# IMU.net
KiCad netlist of a schematic drawn in Altium Designer
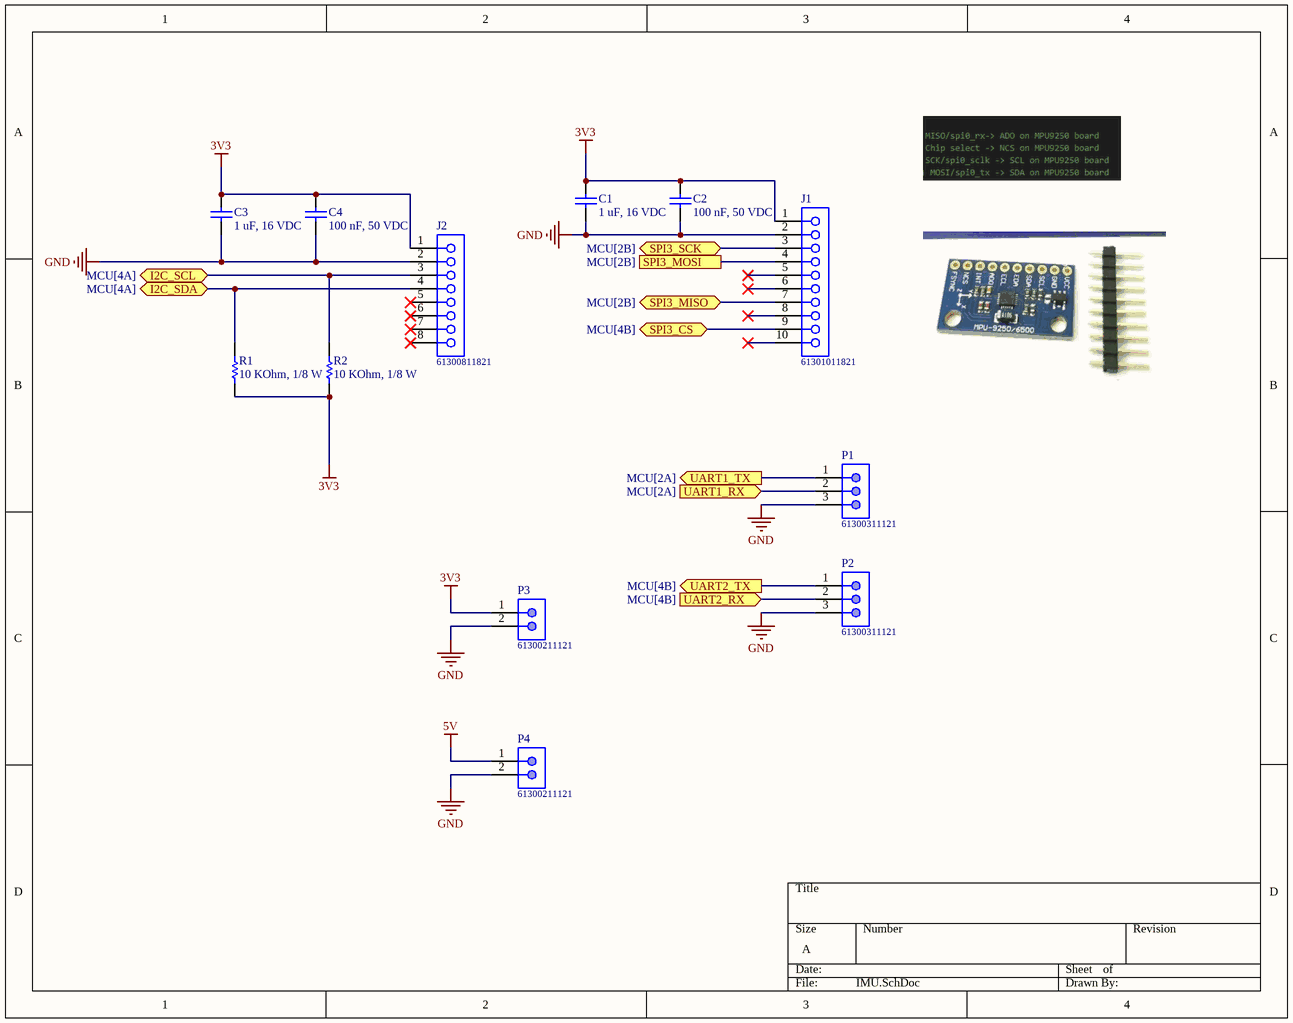
[diagram p0: IMU.SchDoc]

(export (version "E")
  (design (tool "Eeschema 10.0.6"))
  (components
    (comp (ref "C1")
      (value "1 uF, 16 VDC")
      (footprint "CAP_0805")
      (description "CAP, size 0805, 1 uF, 16 VDC")
      (fields (field (name "TOLERANCE") "+/-10%"))
      (libsource (lib "Altium_Ceramic_Cap") (part "0108051051016"))
    )
    (comp (ref "C2")
      (value "100 nF, 50 VDC")
      (footprint "CAP_0805")
      (description "CAP, size 0805, 100 nF, 50 VDC")
      (fields (field (name "TOLERANCE") "+/-5%"))
      (libsource (lib "Altium_Ceramic_Cap") (part "0108051031050"))
    )
    (comp (ref "C3")
      (value "1 uF, 16 VDC")
      (footprint "CAP_0805")
      (description "CAP, size 0805, 1 uF, 16 VDC")
      (fields (field (name "TOLERANCE") "+/-10%"))
      (libsource (lib "Altium_Ceramic_Cap") (part "0108051051016"))
    )
    (comp (ref "C4")
      (value "100 nF, 50 VDC")
      (footprint "CAP_0805")
      (description "CAP, size 0805, 100 nF, 50 VDC")
      (fields (field (name "TOLERANCE") "+/-5%"))
      (libsource (lib "Altium_Ceramic_Cap") (part "0108051031050"))
    )
    (comp (ref "J1")
      (value "61301011821")
      (footprint "61301011821")
      (description "WR-PHD Socket Header, THT, pitch 2.54mm, Single Row, Vertical, 10p")
      (fields (field (name "MANUFACTURER") "Wurth Elektronik"))
      (libsource (lib "Altium_Header") (part "61301011821"))
    )
    (comp (ref "J2")
      (value "61300811821")
      (footprint "61300811821")
      (description "WR-PHD Socket Header, THT, pitch 2.54mm, Single Row, Vertical, 8p")
      (fields (field (name "MANUFACTURER") "Wurth Elektronik"))
      (libsource (lib "Altium_Header") (part "61300811821"))
    )
    (comp (ref "P1")
      (value "61300311121")
      (footprint "61300311121")
      (description "WR-PHD Pin Header, THT, pitch 2.54mm, Single Row, Vertical, 3p")
      (fields (field (name "MANUFACTURER") "Wurth Elektronik"))
      (libsource (lib "Altium_Header") (part "61300311121"))
    )
    (comp (ref "P2")
      (value "61300311121")
      (footprint "61300311121")
      (description "WR-PHD Pin Header, THT, pitch 2.54mm, Single Row, Vertical, 3p")
      (fields (field (name "MANUFACTURER") "Wurth Elektronik"))
      (libsource (lib "Altium_Header") (part "61300311121"))
    )
    (comp (ref "P3")
      (value "61300211121")
      (footprint "61300211121")
      (description "WR-PHD Pin Header, THT, pitch 2.54mm, Single Row, Vertical, 2p")
      (fields (field (name "MANUFACTURER") "Wurth Elektronik"))
      (libsource (lib "Altium_Header") (part "61300211121"))
    )
    (comp (ref "P4")
      (value "61300211121")
      (footprint "61300211121")
      (description "WR-PHD Pin Header, THT, pitch 2.54mm, Single Row, Vertical, 2p")
      (fields (field (name "MANUFACTURER") "Wurth Elektronik"))
      (libsource (lib "Altium_Header") (part "61300211121"))
    )
    (comp (ref "R1")
      (value "10 KOhm, 1/8 W")
      (footprint "RESISTOR_0805")
      (description "RES, size 0805, 10 KOhm, 1/8 W")
      (libsource (lib "Altium_Resistor") (part "0008051031"))
    )
    (comp (ref "R2")
      (value "10 KOhm, 1/8 W")
      (footprint "RESISTOR_0805")
      (description "RES, size 0805, 10 KOhm, 1/8 W")
      (libsource (lib "Altium_Resistor") (part "0008051031"))
    )
  )
  (nets
    (net (code "1") (name "/I2C_SCL") (class "Default")
      (node (ref "J2") (pin "3") (pinfunction "3_3") (pintype "passive"))
      (node (ref "R2") (pin "2") (pinfunction "2_2") (pintype "passive"))
    )
    (net (code "2") (name "/I2C_SDA") (class "Default")
      (node (ref "J2") (pin "4") (pinfunction "4_4") (pintype "passive"))
      (node (ref "R1") (pin "2") (pinfunction "2_2") (pintype "passive"))
    )
    (net (code "3") (name "/SPI3_CS") (class "Default")
      (node (ref "J1") (pin "9") (pinfunction "9_9") (pintype "passive"))
    )
    (net (code "4") (name "/SPI3_MISO") (class "Default")
      (node (ref "J1") (pin "7") (pinfunction "7_7") (pintype "passive"))
    )
    (net (code "5") (name "/SPI3_MOSI") (class "Default")
      (node (ref "J1") (pin "4") (pinfunction "4_4") (pintype "passive"))
    )
    (net (code "6") (name "/SPI3_SCK") (class "Default")
      (node (ref "J1") (pin "3") (pinfunction "3_3") (pintype "passive"))
    )
    (net (code "7") (name "/UART1_RX") (class "Default")
      (node (ref "P1") (pin "2") (pinfunction "2_2") (pintype "passive"))
    )
    (net (code "8") (name "/UART1_TX") (class "Default")
      (node (ref "P1") (pin "1") (pinfunction "1_1") (pintype "passive"))
    )
    (net (code "9") (name "/UART2_RX") (class "Default")
      (node (ref "P2") (pin "2") (pinfunction "2_2") (pintype "passive"))
    )
    (net (code "10") (name "/UART2_TX") (class "Default")
      (node (ref "P2") (pin "1") (pinfunction "1_1") (pintype "passive"))
    )
    (net (code "11") (name "3V3") (class "Default")
      (node (ref "C1") (pin "2") (pinfunction "2_2") (pintype "passive"))
      (node (ref "C2") (pin "2") (pinfunction "2_2") (pintype "passive"))
      (node (ref "C3") (pin "2") (pinfunction "2_2") (pintype "passive"))
      (node (ref "C4") (pin "2") (pinfunction "2_2") (pintype "passive"))
      (node (ref "J1") (pin "1") (pinfunction "1_1") (pintype "passive"))
      (node (ref "J2") (pin "1") (pinfunction "1_1") (pintype "passive"))
      (node (ref "P3") (pin "1") (pinfunction "1_1") (pintype "passive"))
      (node (ref "R1") (pin "1") (pinfunction "1_1") (pintype "passive"))
      (node (ref "R2") (pin "1") (pinfunction "1_1") (pintype "passive"))
    )
    (net (code "12") (name "5V") (class "Default")
      (node (ref "P4") (pin "1") (pinfunction "1_1") (pintype "passive"))
    )
    (net (code "13") (name "GND") (class "Default")
      (node (ref "C1") (pin "1") (pinfunction "1_1") (pintype "passive"))
      (node (ref "C2") (pin "1") (pinfunction "1_1") (pintype "passive"))
      (node (ref "C3") (pin "1") (pinfunction "1_1") (pintype "passive"))
      (node (ref "C4") (pin "1") (pinfunction "1_1") (pintype "passive"))
      (node (ref "J1") (pin "2") (pinfunction "2_2") (pintype "passive"))
      (node (ref "J2") (pin "2") (pinfunction "2_2") (pintype "passive"))
      (node (ref "P1") (pin "3") (pinfunction "3_3") (pintype "passive"))
      (node (ref "P2") (pin "3") (pinfunction "3_3") (pintype "passive"))
      (node (ref "P3") (pin "2") (pinfunction "2_2") (pintype "passive"))
      (node (ref "P4") (pin "2") (pinfunction "2_2") (pintype "passive"))
    )
    (net (code "14") (name "unconnected-(J1-Pad5)") (class "Default")
      (node (ref "J1") (pin "5") (pinfunction "5_5") (pintype "passive+no_connect"))
    )
    (net (code "15") (name "unconnected-(J1-Pad6)") (class "Default")
      (node (ref "J1") (pin "6") (pinfunction "6_6") (pintype "passive+no_connect"))
    )
    (net (code "16") (name "unconnected-(J1-Pad8)") (class "Default")
      (node (ref "J1") (pin "8") (pinfunction "8_8") (pintype "passive+no_connect"))
    )
    (net (code "17") (name "unconnected-(J1-Pad10)") (class "Default")
      (node (ref "J1") (pin "10") (pinfunction "10_10") (pintype "passive+no_connect"))
    )
    (net (code "18") (name "unconnected-(J2-Pad5)") (class "Default")
      (node (ref "J2") (pin "5") (pinfunction "5_5") (pintype "passive+no_connect"))
    )
    (net (code "19") (name "unconnected-(J2-Pad6)") (class "Default")
      (node (ref "J2") (pin "6") (pinfunction "6_6") (pintype "passive+no_connect"))
    )
    (net (code "20") (name "unconnected-(J2-Pad7)") (class "Default")
      (node (ref "J2") (pin "7") (pinfunction "7_7") (pintype "passive+no_connect"))
    )
    (net (code "21") (name "unconnected-(J2-Pad8)") (class "Default")
      (node (ref "J2") (pin "8") (pinfunction "8_8") (pintype "passive+no_connect"))
    )
  )
)
